# Sheet2.net
KiCad netlist of a schematic drawn in Altium Designer
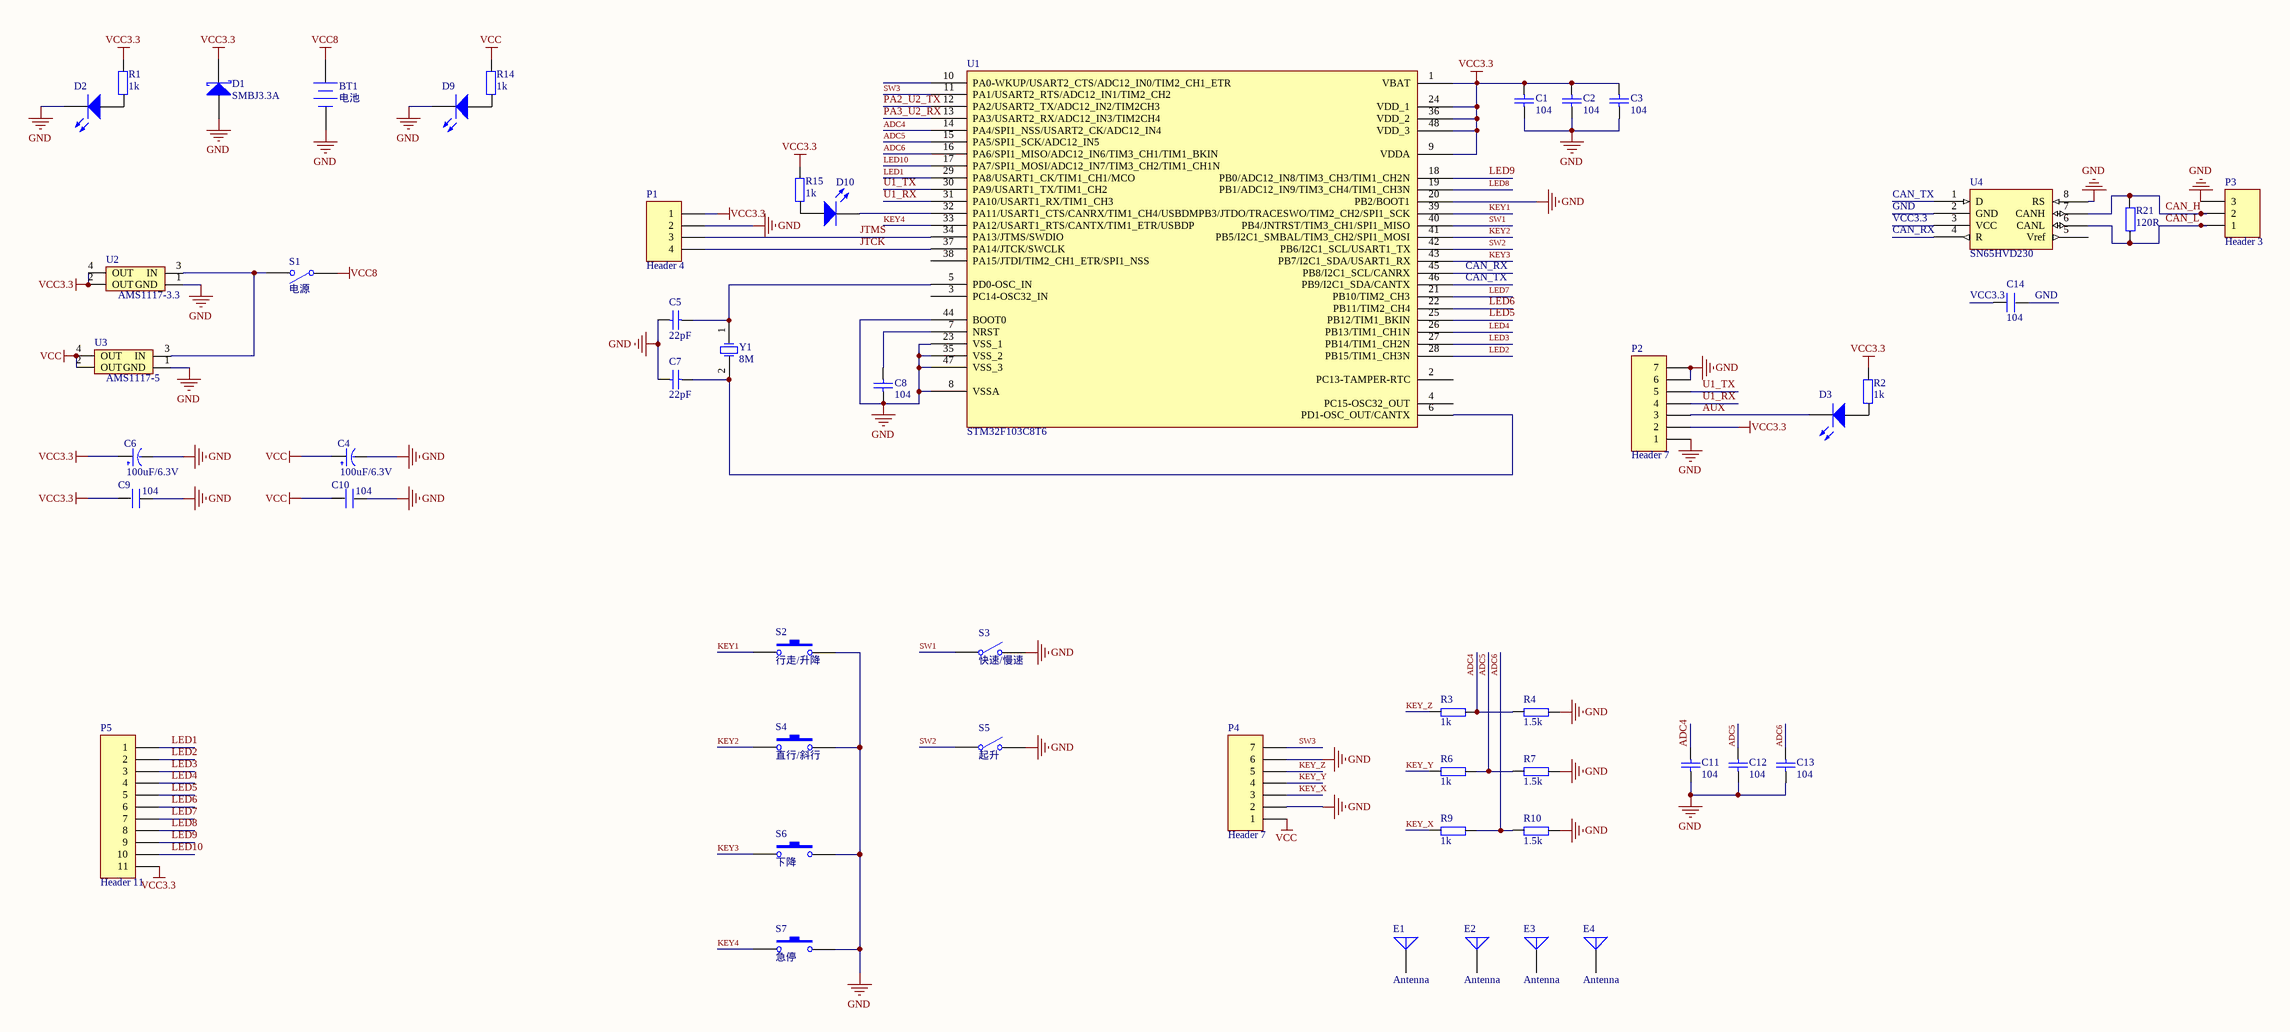
[diagram p0: Sheet2.SchDoc]

(export (version "E")
  (design (tool "Eeschema 10.0.6"))
  (components
    (comp (ref "BT1")
      (value "电池")
      (footprint "DZ-3-3.5")
      (description "Multicell Battery")
      (fields (field (name "PUBLISHER") "Altium Limited"))
      (libsource (lib "Miscellaneous Devices") (part "Battery"))
    )
    (comp (ref "C1")
      (value "104")
      (footprint "0805_C")
      (description "Capacitor")
      (fields (field (name "PUBLISHER") "Altium Limited"))
      (libsource (lib "Miscellaneous Devices") (part "Cap"))
    )
    (comp (ref "C2")
      (value "104")
      (footprint "0805_C")
      (description "Capacitor")
      (fields (field (name "PUBLISHER") "Altium Limited"))
      (libsource (lib "Miscellaneous Devices") (part "Cap"))
    )
    (comp (ref "C3")
      (value "104")
      (footprint "0805_C")
      (description "Capacitor")
      (fields (field (name "PUBLISHER") "Altium Limited"))
      (libsource (lib "Miscellaneous Devices") (part "Cap"))
    )
    (comp (ref "C4") (value "100uF/6.3V") (footprint "3216") (libsource (lib "WarShip V3_SCH") (part "CAP")))
    (comp (ref "C5")
      (value "22pF")
      (footprint "0805_C")
      (description "Capacitor")
      (fields (field (name "PUBLISHER") "Altium Limited"))
      (libsource (lib "Miscellaneous Devices") (part "Cap"))
    )
    (comp (ref "C6") (value "100uF/6.3V") (footprint "3216") (libsource (lib "WarShip V3_SCH") (part "CAP")))
    (comp (ref "C7")
      (value "22pF")
      (footprint "0805_C")
      (description "Capacitor")
      (fields (field (name "PUBLISHER") "Altium Limited"))
      (libsource (lib "Miscellaneous Devices") (part "Cap"))
    )
    (comp (ref "C8")
      (value "104")
      (footprint "0805_C")
      (description "Capacitor")
      (fields (field (name "PUBLISHER") "Altium Limited"))
      (libsource (lib "Miscellaneous Devices") (part "Cap"))
    )
    (comp (ref "C9") (value "104") (footprint "0805_C") (libsource (lib "WarShip V3_SCH") (part "C")))
    (comp (ref "C10") (value "104") (footprint "0805_C") (libsource (lib "WarShip V3_SCH") (part "C")))
    (comp (ref "C11")
      (value "104")
      (footprint "0805_C")
      (description "Capacitor")
      (fields (field (name "PUBLISHER") "Altium Limited"))
      (libsource (lib "Miscellaneous Devices") (part "Cap"))
    )
    (comp (ref "C12")
      (value "104")
      (footprint "0805_C")
      (description "Capacitor")
      (fields (field (name "PUBLISHER") "Altium Limited"))
      (libsource (lib "Miscellaneous Devices") (part "Cap"))
    )
    (comp (ref "C13")
      (value "104")
      (footprint "0805_C")
      (description "Capacitor")
      (fields (field (name "PUBLISHER") "Altium Limited"))
      (libsource (lib "Miscellaneous Devices") (part "Cap"))
    )
    (comp (ref "C14")
      (value "104")
      (footprint "0603_C")
      (libsource (lib "Explorer STM32F407封装库") (part "C_3"))
    )
    (comp (ref "D1")
      (value "SMBJ3.3A")
      (footprint "SMB(DO-214AA)_S1")
      (description "Schottky Rectifier")
      (fields (field (name "PUBLISHER") "Altium Limited"))
      (libsource (lib "Miscellaneous Devices") (part "Diode 18TQ045"))
    )
    (comp (ref "D2")
      (value "LED0")
      (footprint "LC-0805_LED_S1")
      (description "Typical INFRARED GaAs LED")
      (fields (field (name "PUBLISHER") "Altium Limited"))
      (libsource (lib "继电器板_1") (part "LED0"))
    )
    (comp (ref "D3")
      (value "LED0")
      (footprint "LC-0805_LED_S1")
      (description "Typical INFRARED GaAs LED")
      (fields (field (name "PUBLISHER") "Altium Limited"))
      (libsource (lib "继电器板_1") (part "LED0"))
    )
    (comp (ref "D9")
      (value "LED0")
      (footprint "LC-0805_LED_S1")
      (description "Typical INFRARED GaAs LED")
      (fields (field (name "PUBLISHER") "Altium Limited"))
      (libsource (lib "继电器板_1") (part "LED0"))
    )
    (comp (ref "D10")
      (value "LED0")
      (footprint "LC-0805_LED_S1")
      (description "Typical INFRARED GaAs LED")
      (fields (field (name "PUBLISHER") "Altium Limited"))
      (libsource (lib "继电器板_1") (part "LED0"))
    )
    (comp (ref "E1")
      (value "Antenna")
      (footprint "定位孔 Φ3.2")
      (description "Generic Antenna")
      (fields (field (name "PUBLISHER") "Altium Limited"))
      (libsource (lib "Miscellaneous Devices") (part "Antenna"))
    )
    (comp (ref "E2")
      (value "Antenna")
      (footprint "定位孔 Φ3.2")
      (description "Generic Antenna")
      (fields (field (name "PUBLISHER") "Altium Limited"))
      (libsource (lib "Miscellaneous Devices") (part "Antenna"))
    )
    (comp (ref "E3")
      (value "Antenna")
      (footprint "定位孔 Φ3.2")
      (description "Generic Antenna")
      (fields (field (name "PUBLISHER") "Altium Limited"))
      (libsource (lib "Miscellaneous Devices") (part "Antenna"))
    )
    (comp (ref "E4")
      (value "Antenna")
      (footprint "定位孔 Φ3.2")
      (description "Generic Antenna")
      (fields (field (name "PUBLISHER") "Altium Limited"))
      (libsource (lib "Miscellaneous Devices") (part "Antenna"))
    )
    (comp (ref "P1")
      (value "Header 4")
      (footprint "IDE4")
      (description "Header, 4-Pin")
      (fields (field (name "PUBLISHER") "Altium Limited"))
      (libsource (lib "Miscellaneous Connectors") (part "Header 4"))
    )
    (comp (ref "P2")
      (value "Header 7")
      (footprint "AS50-T27")
      (description "Header, 7-Pin")
      (fields (field (name "PUBLISHER") "Altium Limited"))
      (libsource (lib "Miscellaneous Connectors") (part "Header 7"))
    )
    (comp (ref "P3")
      (value "Header 3")
      (footprint "DZ-3-3.5")
      (description "Header, 3-Pin")
      (fields (field (name "PUBLISHER") "Altium Limited"))
      (libsource (lib "Miscellaneous Connectors") (part "Header 3"))
    )
    (comp (ref "P4")
      (value "Header 7")
      (footprint "XH7")
      (description "Header, 7-Pin")
      (fields (field (name "PUBLISHER") "Altium Limited"))
      (libsource (lib "Miscellaneous Connectors") (part "Header 7"))
    )
    (comp (ref "P5")
      (value "Header 11")
      (footprint "XH11")
      (description "Header, 11-Pin")
      (fields (field (name "PUBLISHER") "Altium Limited"))
      (libsource (lib "Miscellaneous Connectors") (part "Header 11"))
    )
    (comp (ref "R1") (value "1k") (footprint "0603_R") (libsource (lib "Explorer STM32F407封装库") (part "R_2")))
    (comp (ref "R2") (value "1k") (footprint "0603_R") (libsource (lib "Explorer STM32F407封装库") (part "R_2")))
    (comp (ref "R3") (value "1k") (footprint "0603_R") (libsource (lib "Explorer STM32F407封装库") (part "R_2")))
    (comp (ref "R4")
      (value "1.5k")
      (footprint "0603_R")
      (libsource (lib "Explorer STM32F407封装库") (part "R_2"))
    )
    (comp (ref "R6") (value "1k") (footprint "0603_R") (libsource (lib "Explorer STM32F407封装库") (part "R_2")))
    (comp (ref "R7")
      (value "1.5k")
      (footprint "0603_R")
      (libsource (lib "Explorer STM32F407封装库") (part "R_2"))
    )
    (comp (ref "R9") (value "1k") (footprint "0603_R") (libsource (lib "Explorer STM32F407封装库") (part "R_2")))
    (comp (ref "R10")
      (value "1.5k")
      (footprint "0603_R")
      (libsource (lib "Explorer STM32F407封装库") (part "R_2"))
    )
    (comp (ref "R14")
      (value "1k")
      (footprint "0603_R")
      (libsource (lib "Explorer STM32F407封装库") (part "R_2"))
    )
    (comp (ref "R15")
      (value "1k")
      (footprint "0603_R")
      (libsource (lib "Explorer STM32F407封装库") (part "R_2"))
    )
    (comp (ref "R21")
      (value "120R")
      (footprint "0603_R")
      (libsource (lib "Explorer STM32F407封装库") (part "R_2"))
    )
    (comp (ref "S1")
      (value "电源")
      (footprint "DZ-3-3.5")
      (description "Single-Pole, Single-Throw Switch")
      (fields (field (name "PUBLISHER") "Altium Limited"))
      (libsource (lib "Miscellaneous Devices") (part "SW-SPST"))
    )
    (comp (ref "S2")
      (value "行走/升降")
      (footprint "DZ-3-3.5")
      (description "Switch")
      (fields (field (name "PUBLISHER") "Altium Limited"))
      (libsource (lib "Miscellaneous Devices") (part "SW-PB"))
    )
    (comp (ref "S3")
      (value "快速/慢速")
      (footprint "DZ-3-3.5")
      (description "Single-Pole, Single-Throw Switch")
      (fields (field (name "PUBLISHER") "Altium Limited"))
      (libsource (lib "Miscellaneous Devices") (part "SW-SPST"))
    )
    (comp (ref "S4")
      (value "直行/斜行")
      (footprint "DZ-3-3.5")
      (description "Switch")
      (fields (field (name "PUBLISHER") "Altium Limited"))
      (libsource (lib "Miscellaneous Devices") (part "SW-PB"))
    )
    (comp (ref "S5")
      (value "起升")
      (footprint "DZ-3-3.5")
      (description "Single-Pole, Single-Throw Switch")
      (fields (field (name "PUBLISHER") "Altium Limited"))
      (libsource (lib "Miscellaneous Devices") (part "SW-SPST"))
    )
    (comp (ref "S6")
      (value "下降")
      (footprint "DZ-3-3.5")
      (description "Switch")
      (fields (field (name "PUBLISHER") "Altium Limited"))
      (libsource (lib "Miscellaneous Devices") (part "SW-PB"))
    )
    (comp (ref "S7")
      (value "急停")
      (footprint "DZ-3-3.5")
      (description "Switch")
      (fields (field (name "PUBLISHER") "Altium Limited"))
      (libsource (lib "Miscellaneous Devices") (part "SW-PB"))
    )
    (comp (ref "U1")
      (value "STM32F103C8T6")
      (footprint "LQFP-48_7x7x05P")
      (libsource (lib "Schlib1") (part "stm32f103v8t6"))
    )
    (comp (ref "U2")
      (value "AMS1117-3.3")
      (footprint "LC-SOT-223")
      (libsource (lib "WarShip V3_SCH") (part "AMS1117"))
    )
    (comp (ref "U3")
      (value "AMS1117-5")
      (footprint "LC-SOT-223")
      (libsource (lib "WarShip V3_SCH") (part "AMS1117"))
    )
    (comp (ref "U4")
      (value "SN65HVD230")
      (footprint "LC-SOIC-8_150mil")
      (libsource (lib "Explorer STM32F407封装库") (part "SN65HVD230D"))
    )
    (comp (ref "Y1")
      (value "8M")
      (footprint "XTAL_US")
      (description "Crystal Oscillator")
      (fields (field (name "PUBLISHER") "Altium Limited"))
      (libsource (lib "Miscellaneous Devices") (part "XTAL"))
    )
  )
  (nets
    (net (code "1") (name "/ADC4") (class "Default")
      (node (ref "C11") (pin "2") (pinfunction "2_2") (pintype "passive"))
      (node (ref "R3") (pin "2") (pintype "passive"))
      (node (ref "R4") (pin "1") (pintype "passive"))
      (node (ref "U1") (pin "14") (pinfunction "PA4/SPI1_NSS/USART2_CK/ADC12_IN4_14") (pintype "passive"))
    )
    (net (code "2") (name "/ADC5") (class "Default")
      (node (ref "C12") (pin "1") (pinfunction "1_1") (pintype "passive"))
      (node (ref "R6") (pin "2") (pintype "passive"))
      (node (ref "R7") (pin "1") (pintype "passive"))
      (node (ref "U1") (pin "15") (pinfunction "PA5/SPI1_SCK/ADC12_IN5_15") (pintype "passive"))
    )
    (net (code "3") (name "/ADC6") (class "Default")
      (node (ref "C13") (pin "1") (pinfunction "1_1") (pintype "passive"))
      (node (ref "R10") (pin "1") (pintype "passive"))
      (node (ref "R9") (pin "2") (pintype "passive"))
      (node (ref "U1") (pin "16") (pinfunction "PA6/SPI1_MISO/ADC12_IN6/TIM3_CH1/TIM1_BKIN_16") (pintype "passive"))
    )
    (net (code "4") (name "/AUX") (class "Default")
      (node (ref "D3") (pin "K") (pinfunction "K_K") (pintype "passive"))
      (node (ref "P2") (pin "3") (pinfunction "3_3") (pintype "passive"))
    )
    (net (code "5") (name "/CAN_H") (class "Default")
      (node (ref "P3") (pin "2") (pinfunction "2_2") (pintype "passive"))
      (node (ref "R21") (pin "2") (pintype "passive"))
      (node (ref "U4") (pin "7") (pinfunction "CANH_7") (pintype "bidirectional"))
    )
    (net (code "6") (name "/CAN_L") (class "Default")
      (node (ref "P3") (pin "1") (pinfunction "1_1") (pintype "passive"))
      (node (ref "R21") (pin "1") (pintype "passive"))
      (node (ref "U4") (pin "6") (pinfunction "CANL_6") (pintype "bidirectional"))
    )
    (net (code "7") (name "/CAN_RX") (class "Default")
      (node (ref "U1") (pin "45") (pinfunction "PB8/I2C1_SCL/CANRX_45") (pintype "passive"))
      (node (ref "U4") (pin "4") (pinfunction "R_4") (pintype "output"))
    )
    (net (code "8") (name "/CAN_TX") (class "Default")
      (node (ref "U1") (pin "46") (pinfunction "PB9/I2C1_SDA/CANTX_46") (pintype "passive"))
      (node (ref "U4") (pin "1") (pinfunction "D_1") (pintype "input"))
    )
    (net (code "9") (name "/JTCK") (class "Default")
      (node (ref "P1") (pin "4") (pinfunction "4_4") (pintype "passive"))
      (node (ref "U1") (pin "37") (pinfunction "PA14/JTCK/SWCLK_37") (pintype "passive"))
    )
    (net (code "10") (name "/JTMS") (class "Default")
      (node (ref "P1") (pin "3") (pinfunction "3_3") (pintype "passive"))
      (node (ref "U1") (pin "34") (pinfunction "PA13/JTMS/SWDIO_34") (pintype "passive"))
    )
    (net (code "11") (name "/KEY1") (class "Default")
      (node (ref "S2") (pin "1") (pinfunction "1_1") (pintype "passive"))
      (node (ref "U1") (pin "39") (pinfunction "PB3/JTDO/TRACESWO/TIM2_CH2/SPI1_SCK_39") (pintype "passive"))
    )
    (net (code "12") (name "/KEY2") (class "Default")
      (node (ref "S4") (pin "1") (pinfunction "1_1") (pintype "passive"))
      (node (ref "U1") (pin "41") (pinfunction "PB5/I2C1_SMBAL/TIM3_CH2/SPI1_MOSI_41") (pintype "passive"))
    )
    (net (code "13") (name "/KEY3") (class "Default")
      (node (ref "S6") (pin "1") (pinfunction "1_1") (pintype "passive"))
      (node (ref "U1") (pin "43") (pinfunction "PB7/I2C1_SDA/USART1_RX_43") (pintype "passive"))
    )
    (net (code "14") (name "/KEY4") (class "Default")
      (node (ref "S7") (pin "1") (pinfunction "1_1") (pintype "passive"))
      (node (ref "U1") (pin "33") (pinfunction "PA12/USART1_RTS/CANTX/TIM1_ETR/USBDP_33") (pintype "passive"))
    )
    (net (code "15") (name "/KEY_X") (class "Default")
      (node (ref "P4") (pin "3") (pinfunction "3_3") (pintype "passive"))
      (node (ref "R9") (pin "1") (pintype "passive"))
    )
    (net (code "16") (name "/KEY_Y") (class "Default")
      (node (ref "P4") (pin "4") (pinfunction "4_4") (pintype "passive"))
      (node (ref "R6") (pin "1") (pintype "passive"))
    )
    (net (code "17") (name "/KEY_Z") (class "Default")
      (node (ref "P4") (pin "5") (pinfunction "5_5") (pintype "passive"))
      (node (ref "R3") (pin "1") (pintype "passive"))
    )
    (net (code "18") (name "/LED1") (class "Default")
      (node (ref "P5") (pin "1") (pinfunction "1_1") (pintype "passive"))
      (node (ref "U1") (pin "29") (pinfunction "PA8/USART1_CK/TIM1_CH1/MCO_29") (pintype "passive"))
    )
    (net (code "19") (name "/LED2") (class "Default")
      (node (ref "P5") (pin "2") (pinfunction "2_2") (pintype "passive"))
      (node (ref "U1") (pin "28") (pinfunction "PB15/TIM1_CH3N_28") (pintype "passive"))
    )
    (net (code "20") (name "/LED3") (class "Default")
      (node (ref "P5") (pin "3") (pinfunction "3_3") (pintype "passive"))
      (node (ref "U1") (pin "27") (pinfunction "PB14/TIM1_CH2N_27") (pintype "passive"))
    )
    (net (code "21") (name "/LED4") (class "Default")
      (node (ref "P5") (pin "4") (pinfunction "4_4") (pintype "passive"))
      (node (ref "U1") (pin "26") (pinfunction "PB13/TIM1_CH1N_26") (pintype "passive"))
    )
    (net (code "22") (name "/LED5") (class "Default")
      (node (ref "P5") (pin "5") (pinfunction "5_5") (pintype "passive"))
      (node (ref "U1") (pin "25") (pinfunction "PB12/TIM1_BKIN_25") (pintype "passive"))
    )
    (net (code "23") (name "/LED6") (class "Default")
      (node (ref "P5") (pin "6") (pinfunction "6_6") (pintype "passive"))
      (node (ref "U1") (pin "22") (pinfunction "PB11/TIM2_CH4_22") (pintype "passive"))
    )
    (net (code "24") (name "/LED7") (class "Default")
      (node (ref "P5") (pin "7") (pinfunction "7_7") (pintype "passive"))
      (node (ref "U1") (pin "21") (pinfunction "PB10/TIM2_CH3_21") (pintype "passive"))
    )
    (net (code "25") (name "/LED8") (class "Default")
      (node (ref "P5") (pin "8") (pinfunction "8_8") (pintype "passive"))
      (node (ref "U1") (pin "19") (pinfunction "PB1/ADC12_IN9/TIM3_CH4/TIM1_CH3N_19") (pintype "passive"))
    )
    (net (code "26") (name "/LED9") (class "Default")
      (node (ref "P5") (pin "9") (pinfunction "9_9") (pintype "passive"))
      (node (ref "U1") (pin "18") (pinfunction "PB0/ADC12_IN8/TIM3_CH3/TIM1_CH2N_18") (pintype "passive"))
    )
    (net (code "27") (name "/LED10") (class "Default")
      (node (ref "P5") (pin "10") (pinfunction "10_10") (pintype "passive"))
      (node (ref "U1") (pin "17") (pinfunction "PA7/SPI1_MOSI/ADC12_IN7/TIM3_CH2/TIM1_CH1N_17") (pintype "passive"))
    )
    (net (code "28") (name "/PA2_U2_TX") (class "Default")
      (node (ref "U1") (pin "12") (pinfunction "PA2/USART2_TX/ADC12_IN2/TIM2CH3_12") (pintype "passive"))
    )
    (net (code "29") (name "/PA3_U2_RX") (class "Default")
      (node (ref "U1") (pin "13") (pinfunction "PA3/USART2_RX/ADC12_IN3/TIM2CH4_13") (pintype "passive"))
    )
    (net (code "30") (name "/SW1") (class "Default")
      (node (ref "S3") (pin "1") (pinfunction "COMMON_1") (pintype "passive"))
      (node (ref "U1") (pin "40") (pinfunction "PB4/JNTRST/TIM3_CH1/SPI1_MISO_40") (pintype "passive"))
    )
    (net (code "31") (name "/SW2") (class "Default")
      (node (ref "S5") (pin "1") (pinfunction "COMMON_1") (pintype "passive"))
      (node (ref "U1") (pin "42") (pinfunction "PB6/I2C1_SCL/USART1_TX_42") (pintype "passive"))
    )
    (net (code "32") (name "/SW3") (class "Default")
      (node (ref "P4") (pin "7") (pinfunction "7_7") (pintype "passive"))
      (node (ref "U1") (pin "11") (pinfunction "PA1/USART2_RTS/ADC12_IN1/TIM2_CH2_11") (pintype "passive"))
    )
    (net (code "33") (name "/U1_RX") (class "Default")
      (node (ref "P2") (pin "4") (pinfunction "4_4") (pintype "passive"))
      (node (ref "U1") (pin "31") (pinfunction "PA10/USART1_RX/TIM1_CH3_31") (pintype "passive"))
    )
    (net (code "34") (name "/U1_TX") (class "Default")
      (node (ref "P2") (pin "5") (pinfunction "5_5") (pintype "passive"))
      (node (ref "U1") (pin "30") (pinfunction "PA9/USART1_TX/TIM1_CH2_30") (pintype "passive"))
    )
    (net (code "35") (name "GND") (class "Default")
      (node (ref "BT1") (pin "2") (pinfunction "-_2") (pintype "passive"))
      (node (ref "C1") (pin "2") (pinfunction "2_2") (pintype "passive"))
      (node (ref "C10") (pin "1") (pintype "passive"))
      (node (ref "C11") (pin "1") (pinfunction "1_1") (pintype "passive"))
      (node (ref "C12") (pin "2") (pinfunction "2_2") (pintype "passive"))
      (node (ref "C13") (pin "2") (pinfunction "2_2") (pintype "passive"))
      (node (ref "C14") (pin "2") (pintype "passive"))
      (node (ref "C2") (pin "2") (pinfunction "2_2") (pintype "passive"))
      (node (ref "C3") (pin "2") (pinfunction "2_2") (pintype "passive"))
      (node (ref "C4") (pin "2") (pinfunction "GND_2") (pintype "passive"))
      (node (ref "C5") (pin "2") (pinfunction "2_2") (pintype "passive"))
      (node (ref "C6") (pin "2") (pinfunction "GND_2") (pintype "passive"))
      (node (ref "C7") (pin "2") (pinfunction "2_2") (pintype "passive"))
      (node (ref "C8") (pin "2") (pinfunction "2_2") (pintype "passive"))
      (node (ref "C9") (pin "1") (pintype "passive"))
      (node (ref "D1") (pin "2") (pinfunction "A_2") (pintype "passive"))
      (node (ref "D2") (pin "K") (pinfunction "K_K") (pintype "passive"))
      (node (ref "D9") (pin "K") (pinfunction "K_K") (pintype "passive"))
      (node (ref "P1") (pin "2") (pinfunction "2_2") (pintype "passive"))
      (node (ref "P2") (pin "1") (pinfunction "1_1") (pintype "passive"))
      (node (ref "P2") (pin "6") (pinfunction "6_6") (pintype "passive"))
      (node (ref "P2") (pin "7") (pinfunction "7_7") (pintype "passive"))
      (node (ref "P3") (pin "3") (pinfunction "3_3") (pintype "passive"))
      (node (ref "P4") (pin "2") (pinfunction "2_2") (pintype "passive"))
      (node (ref "P4") (pin "6") (pinfunction "6_6") (pintype "passive"))
      (node (ref "R10") (pin "2") (pintype "passive"))
      (node (ref "R4") (pin "2") (pintype "passive"))
      (node (ref "R7") (pin "2") (pintype "passive"))
      (node (ref "S2") (pin "2") (pinfunction "2_2") (pintype "passive"))
      (node (ref "S3") (pin "2") (pinfunction "NO_2") (pintype "passive"))
      (node (ref "S4") (pin "2") (pinfunction "2_2") (pintype "passive"))
      (node (ref "S5") (pin "2") (pinfunction "NO_2") (pintype "passive"))
      (node (ref "S6") (pin "2") (pinfunction "2_2") (pintype "passive"))
      (node (ref "S7") (pin "2") (pinfunction "2_2") (pintype "passive"))
      (node (ref "U1") (pin "20") (pinfunction "PB2/BOOT1_20") (pintype "passive"))
      (node (ref "U1") (pin "23") (pinfunction "VSS_1_23") (pintype "passive"))
      (node (ref "U1") (pin "35") (pinfunction "VSS_2_35") (pintype "passive"))
      (node (ref "U1") (pin "44") (pinfunction "BOOT0_44") (pintype "passive"))
      (node (ref "U1") (pin "47") (pinfunction "VSS_3_47") (pintype "passive"))
      (node (ref "U1") (pin "8") (pinfunction "VSSA_8") (pintype "passive"))
      (node (ref "U2") (pin "1") (pinfunction "GND_1") (pintype "passive"))
      (node (ref "U3") (pin "1") (pinfunction "GND_1") (pintype "passive"))
      (node (ref "U4") (pin "2") (pinfunction "GND_2") (pintype "power_in"))
      (node (ref "U4") (pin "8") (pinfunction "RS_8") (pintype "input"))
    )
    (net (code "36") (name "Net-(D2-PadA)") (class "Default")
      (node (ref "D2") (pin "A") (pinfunction "A_A") (pintype "passive"))
      (node (ref "R1") (pin "2") (pintype "passive"))
    )
    (net (code "37") (name "Net-(D3-PadA)") (class "Default")
      (node (ref "D3") (pin "A") (pinfunction "A_A") (pintype "passive"))
      (node (ref "R2") (pin "2") (pintype "passive"))
    )
    (net (code "38") (name "Net-(D9-PadA)") (class "Default")
      (node (ref "D9") (pin "A") (pinfunction "A_A") (pintype "passive"))
      (node (ref "R14") (pin "2") (pintype "passive"))
    )
    (net (code "39") (name "Net-(D10-PadA)") (class "Default")
      (node (ref "D10") (pin "A") (pinfunction "A_A") (pintype "passive"))
      (node (ref "R15") (pin "2") (pintype "passive"))
    )
    (net (code "40") (name "Net-(S1-NO)") (class "Default")
      (node (ref "S1") (pin "2") (pinfunction "NO_2") (pintype "passive"))
      (node (ref "U2") (pin "3") (pinfunction "IN_3") (pintype "passive"))
      (node (ref "U3") (pin "3") (pinfunction "IN_3") (pintype "passive"))
    )
    (net (code "41") (name "Net-(U1-NRST)") (class "Default")
      (node (ref "C8") (pin "1") (pinfunction "1_1") (pintype "passive"))
      (node (ref "U1") (pin "7") (pinfunction "NRST_7") (pintype "passive"))
    )
    (net (code "42") (name "Net-(U1-PA11{slash}USART1_CTS{slash}CANRX{slash}TIM1_CH4{slash}USBDM)") (class "Default")
      (node (ref "D10") (pin "K") (pinfunction "K_K") (pintype "passive"))
      (node (ref "U1") (pin "32") (pinfunction "PA11/USART1_CTS/CANRX/TIM1_CH4/USBDM_32") (pintype "passive"))
    )
    (net (code "43") (name "Net-(U1-PD0-OSC_IN)") (class "Default")
      (node (ref "C5") (pin "1") (pinfunction "1_1") (pintype "passive"))
      (node (ref "U1") (pin "5") (pinfunction "PD0-OSC_IN_5") (pintype "passive"))
      (node (ref "Y1") (pin "1") (pinfunction "OSC1_1") (pintype "passive"))
    )
    (net (code "44") (name "Net-(U1-PD1-OSC_OUT{slash}CANTX)") (class "Default")
      (node (ref "C7") (pin "1") (pinfunction "1_1") (pintype "passive"))
      (node (ref "U1") (pin "6") (pinfunction "PD1-OSC_OUT/CANTX_6") (pintype "passive"))
      (node (ref "Y1") (pin "2") (pinfunction "OSC2_2") (pintype "passive"))
    )
    (net (code "45") (name "VCC") (class "Default")
      (node (ref "C10") (pin "2") (pintype "passive"))
      (node (ref "C4") (pin "1") (pinfunction "VCC_1") (pintype "passive"))
      (node (ref "P4") (pin "1") (pinfunction "1_1") (pintype "passive"))
      (node (ref "R14") (pin "1") (pintype "passive"))
      (node (ref "U3") (pin "2") (pinfunction "OUT_2") (pintype "passive"))
      (node (ref "U3") (pin "4") (pinfunction "OUT_4") (pintype "passive"))
    )
    (net (code "46") (name "VCC3.3") (class "Default")
      (node (ref "C1") (pin "1") (pinfunction "1_1") (pintype "passive"))
      (node (ref "C14") (pin "1") (pintype "passive"))
      (node (ref "C2") (pin "1") (pinfunction "1_1") (pintype "passive"))
      (node (ref "C3") (pin "1") (pinfunction "1_1") (pintype "passive"))
      (node (ref "C6") (pin "1") (pinfunction "VCC_1") (pintype "passive"))
      (node (ref "C9") (pin "2") (pintype "passive"))
      (node (ref "D1") (pin "1") (pinfunction "K_1") (pintype "passive"))
      (node (ref "P1") (pin "1") (pinfunction "1_1") (pintype "passive"))
      (node (ref "P2") (pin "2") (pinfunction "2_2") (pintype "passive"))
      (node (ref "P5") (pin "11") (pinfunction "11_11") (pintype "passive"))
      (node (ref "R1") (pin "1") (pintype "passive"))
      (node (ref "R15") (pin "1") (pintype "passive"))
      (node (ref "R2") (pin "1") (pintype "passive"))
      (node (ref "U1") (pin "1") (pinfunction "VBAT_1") (pintype "passive"))
      (node (ref "U1") (pin "24") (pinfunction "VDD_1_24") (pintype "passive"))
      (node (ref "U1") (pin "36") (pinfunction "VDD_2_36") (pintype "passive"))
      (node (ref "U1") (pin "48") (pinfunction "VDD_3_48") (pintype "passive"))
      (node (ref "U1") (pin "9") (pinfunction "VDDA_9") (pintype "passive"))
      (node (ref "U2") (pin "2") (pinfunction "OUT_2") (pintype "passive"))
      (node (ref "U2") (pin "4") (pinfunction "OUT_4") (pintype "passive"))
      (node (ref "U4") (pin "3") (pinfunction "VCC_3") (pintype "power_in"))
    )
    (net (code "47") (name "VCC8") (class "Default")
      (node (ref "BT1") (pin "1") (pinfunction "+_1") (pintype "passive"))
      (node (ref "S1") (pin "1") (pinfunction "COMMON_1") (pintype "passive"))
    )
    (net (code "48") (name "unconnected-(E1-A-Pad1)") (class "Default")
      (node (ref "E1") (pin "1") (pinfunction "A_1") (pintype "passive"))
    )
    (net (code "49") (name "unconnected-(E2-A-Pad1)") (class "Default")
      (node (ref "E2") (pin "1") (pinfunction "A_1") (pintype "passive"))
    )
    (net (code "50") (name "unconnected-(E3-A-Pad1)") (class "Default")
      (node (ref "E3") (pin "1") (pinfunction "A_1") (pintype "passive"))
    )
    (net (code "51") (name "unconnected-(E4-A-Pad1)") (class "Default")
      (node (ref "E4") (pin "1") (pinfunction "A_1") (pintype "passive"))
    )
    (net (code "52") (name "unconnected-(U1-PA0-WKUP{slash}USART2_CTS{slash}ADC12_IN0{slash}TIM2_CH1_ETR-Pad10)") (class "Default")
      (node (ref "U1") (pin "10") (pinfunction "PA0-WKUP/USART2_CTS/ADC12_IN0/TIM2_CH1_ETR_10") (pintype "passive"))
    )
    (net (code "53") (name "unconnected-(U1-PA15{slash}JTDI{slash}TIM2_CH1_ETR{slash}SPI1_NSS-Pad38)") (class "Default")
      (node (ref "U1") (pin "38") (pinfunction "PA15/JTDI/TIM2_CH1_ETR/SPI1_NSS_38") (pintype "passive"))
    )
    (net (code "54") (name "unconnected-(U1-PC13-TAMPER-RTC-Pad2)") (class "Default")
      (node (ref "U1") (pin "2") (pinfunction "PC13-TAMPER-RTC_2") (pintype "passive"))
    )
    (net (code "55") (name "unconnected-(U1-PC14-OSC32_IN-Pad3)") (class "Default")
      (node (ref "U1") (pin "3") (pinfunction "PC14-OSC32_IN_3") (pintype "passive"))
    )
    (net (code "56") (name "unconnected-(U1-PC15-OSC32_OUT-Pad4)") (class "Default")
      (node (ref "U1") (pin "4") (pinfunction "PC15-OSC32_OUT_4") (pintype "passive"))
    )
    (net (code "57") (name "unconnected-(U4-Vref-Pad5)") (class "Default")
      (node (ref "U4") (pin "5") (pinfunction "Vref_5") (pintype "output"))
    )
  )
)
